# Meteo_shema_32F407.net
KiCad netlist of a schematic drawn in Altium Designer
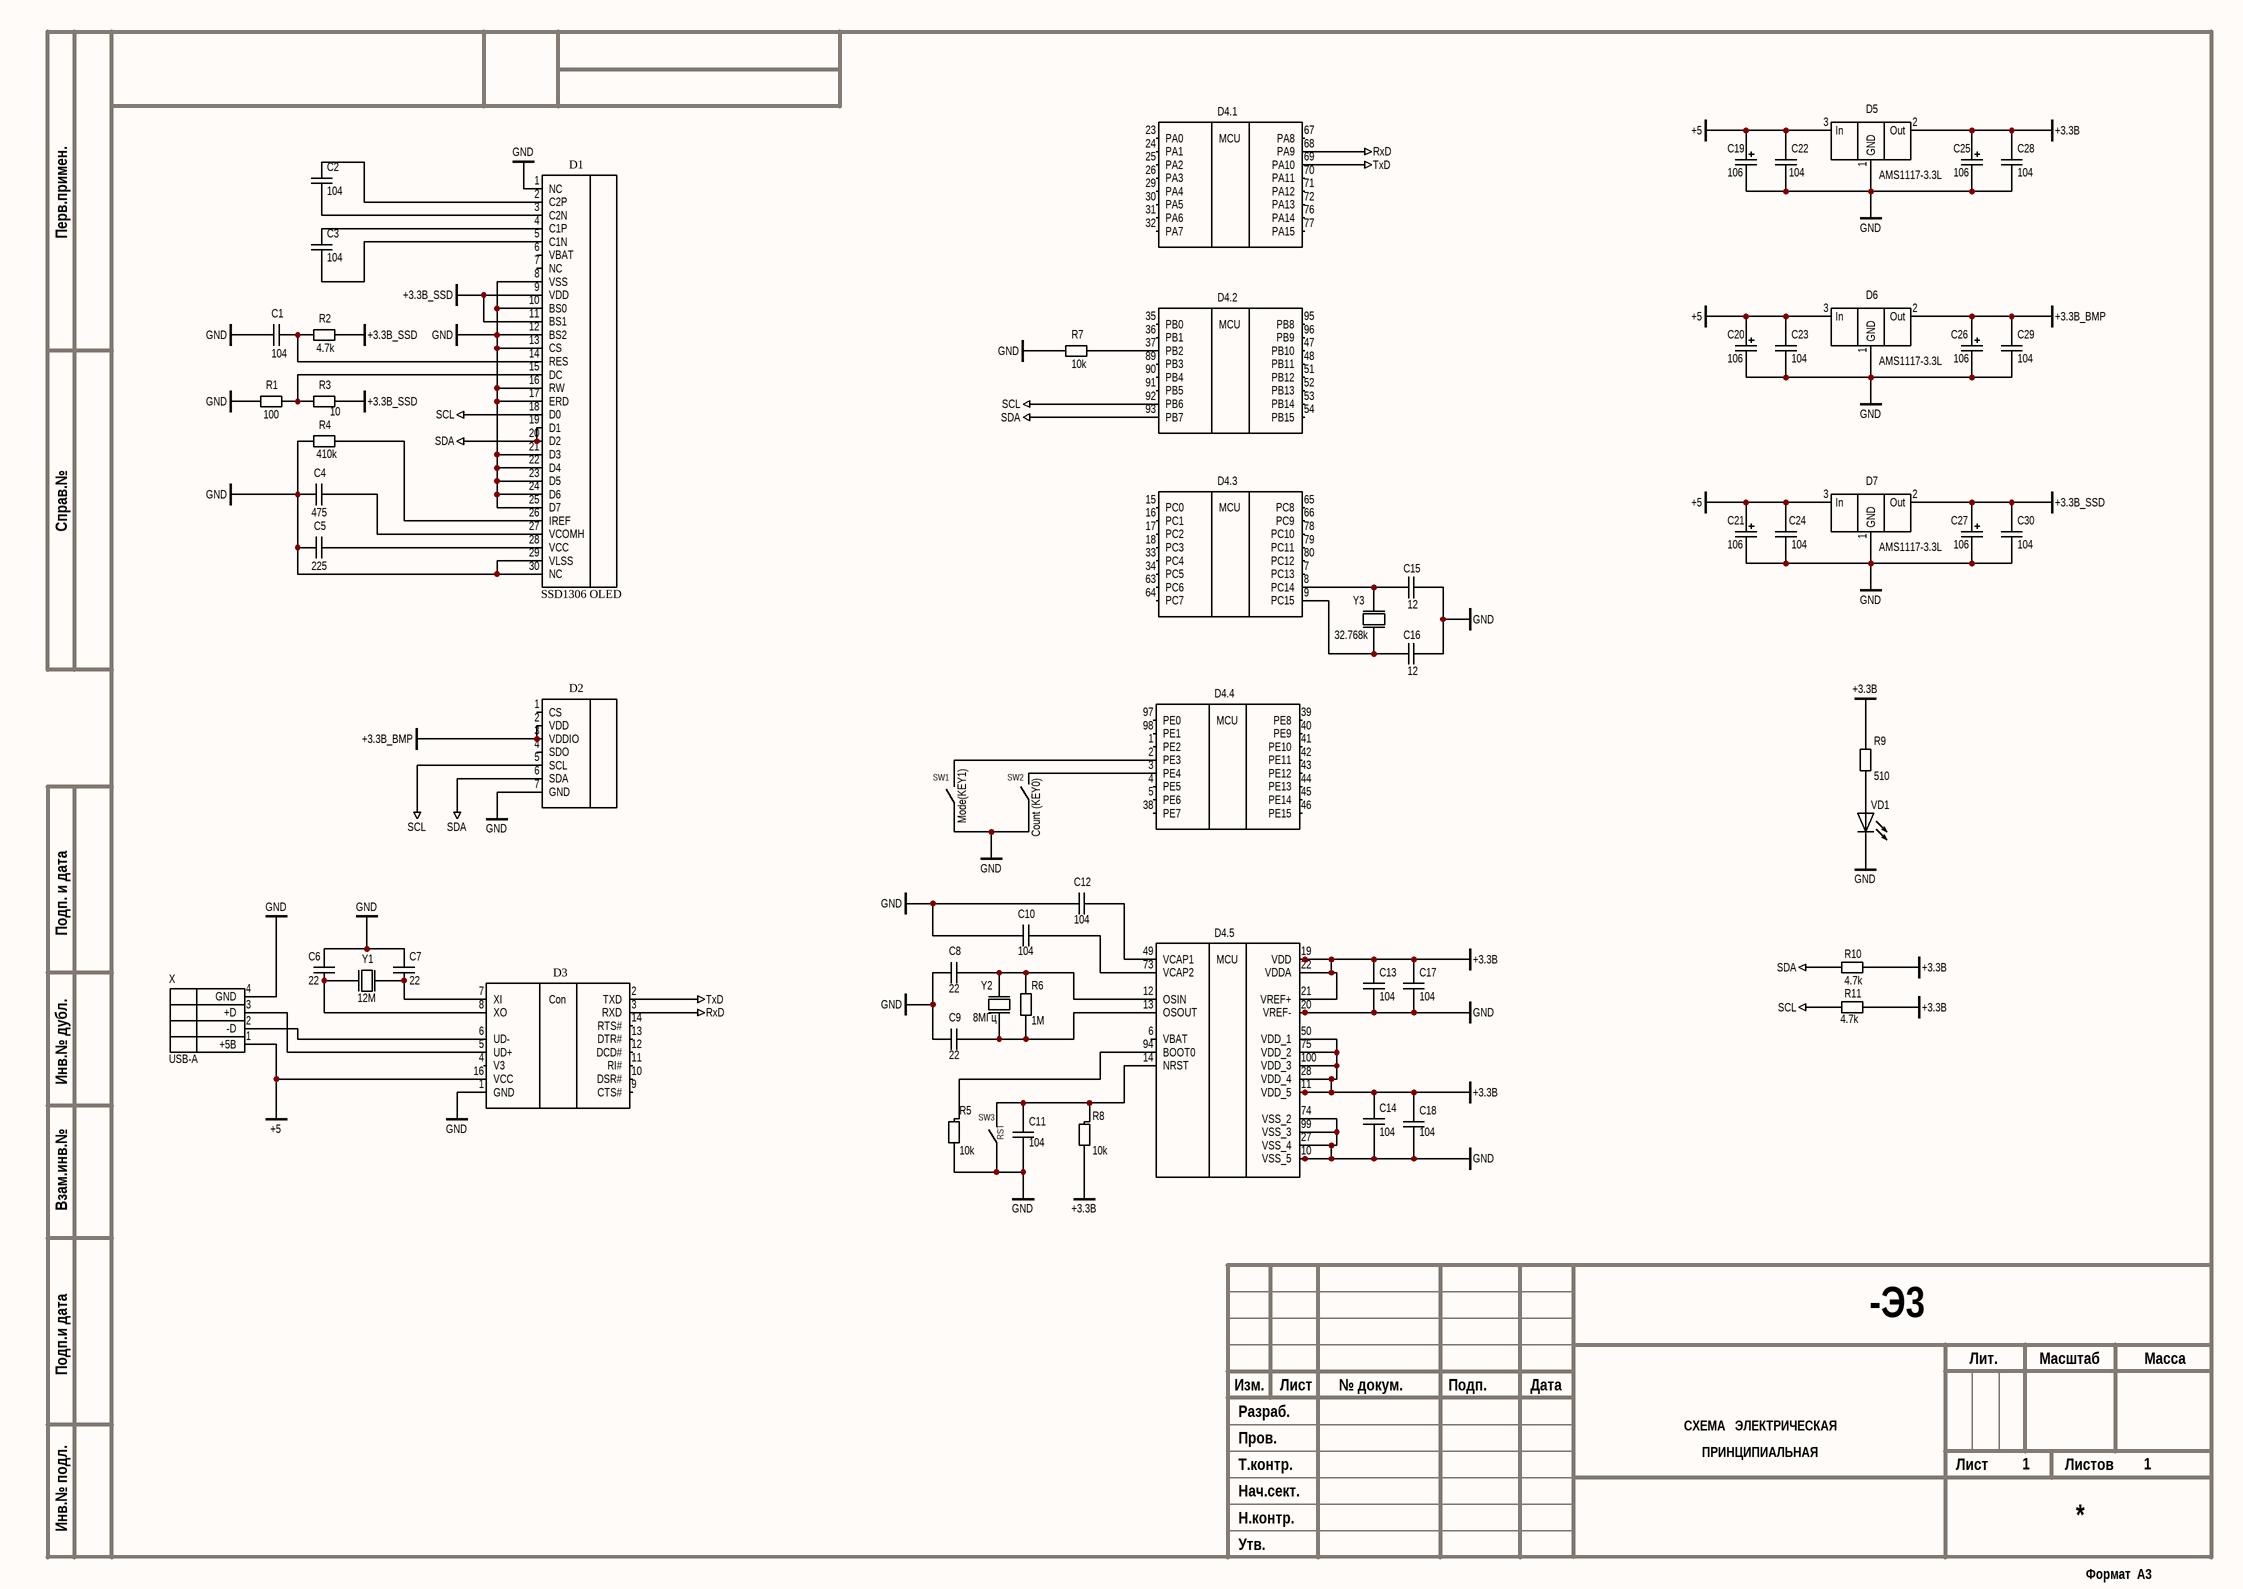
[diagram p0: Meteo_shema_32F407.SchDoc]

(export (version "E")
  (design (tool "Eeschema 10.0.6"))
  (components
    (comp (ref "C1") (value "104") (footprint "0603") (libsource (lib "MainLib") (part "C")))
    (comp (ref "C2") (value "104") (footprint "0603") (libsource (lib "MainLib") (part "C")))
    (comp (ref "C3") (value "104") (footprint "0603") (libsource (lib "MainLib") (part "C")))
    (comp (ref "C4") (value "475") (footprint "0603") (libsource (lib "MainLib") (part "C")))
    (comp (ref "C5") (value "225") (footprint "0603") (libsource (lib "MainLib") (part "C")))
    (comp (ref "C6") (value "22") (footprint "0603") (libsource (lib "MainLib") (part "C")))
    (comp (ref "C7") (value "22") (footprint "0603") (libsource (lib "MainLib") (part "C")))
    (comp (ref "C8") (value "22") (footprint "0603") (libsource (lib "MainLib") (part "C")))
    (comp (ref "C9") (value "22") (footprint "0603") (libsource (lib "MainLib") (part "C")))
    (comp (ref "C11") (value "104") (footprint "0603") (libsource (lib "MainLib") (part "C")))
    (comp (ref "C12") (value "104") (footprint "0603") (libsource (lib "MainLib") (part "C")))
    (comp (ref "C13") (value "104") (footprint "0603") (libsource (lib "MainLib") (part "C")))
    (comp (ref "C14") (value "104") (footprint "0603") (libsource (lib "MainLib") (part "C")))
    (comp (ref "C15") (value "12") (footprint "0603") (libsource (lib "MainLib") (part "C")))
    (comp (ref "C16") (value "12") (footprint "0603") (libsource (lib "MainLib") (part "C")))
    (comp (ref "C17") (value "104") (footprint "0603") (libsource (lib "MainLib") (part "C")))
    (comp (ref "C18") (value "104") (footprint "0603") (libsource (lib "MainLib") (part "C")))
    (comp (ref "C19")
      (value "106")
      (footprint "EIA_6032–28")
      (description "TECAP EIA 6032–28")
      (libsource (lib "MainLib") (part "C+ TECAP"))
    )
    (comp (ref "C20")
      (value "106")
      (footprint "EIA_6032–28")
      (description "TECAP EIA 6032–28")
      (libsource (lib "MainLib") (part "C+ TECAP"))
    )
    (comp (ref "C21")
      (value "106")
      (footprint "EIA_6032–28")
      (description "TECAP EIA 6032–28")
      (libsource (lib "MainLib") (part "C+ TECAP"))
    )
    (comp (ref "C22") (value "104") (footprint "0603") (libsource (lib "MainLib") (part "C")))
    (comp (ref "C23") (value "104") (footprint "0603") (libsource (lib "MainLib") (part "C")))
    (comp (ref "C24") (value "104") (footprint "0603") (libsource (lib "MainLib") (part "C")))
    (comp (ref "C25")
      (value "106")
      (footprint "EIA_6032–28")
      (description "TECAP EIA 6032–28")
      (libsource (lib "MainLib") (part "C+ TECAP"))
    )
    (comp (ref "C26")
      (value "106")
      (footprint "EIA_6032–28")
      (description "TECAP EIA 6032–28")
      (libsource (lib "MainLib") (part "C+ TECAP"))
    )
    (comp (ref "C27")
      (value "106")
      (footprint "EIA_6032–28")
      (description "TECAP EIA 6032–28")
      (libsource (lib "MainLib") (part "C+ TECAP"))
    )
    (comp (ref "C28") (value "104") (footprint "0603") (libsource (lib "MainLib") (part "C")))
    (comp (ref "C29") (value "104") (footprint "0603") (libsource (lib "MainLib") (part "C")))
    (comp (ref "C30") (value "104") (footprint "0603") (libsource (lib "MainLib") (part "C")))
    (comp (ref "D1")
      (value "SSD1306 OLED")
      (footprint "SSD1306")
      (libsource (lib "MainLib") (part "SSD1306 OLED"))
    )
    (comp (ref "D2") (value "BMP180") (footprint "BMP180") (libsource (lib "MainLib") (part "BMP180")))
    (comp (ref "D3") (value "CH340G") (libsource (lib "MainLib") (part "CH340G")))
    (comp (ref "D4")
      (value "STM32F407VE")
      (footprint "LQFP100")
      (description "ARM3")
      (libsource (lib "MainLib") (part "STM32F407VE"))
    )
    (comp (ref "D5")
      (value "AMS1117-3.3L")
      (footprint "SOT223-4N")
      (libsource (lib "MainLib") (part "AMS1117-3.3L"))
    )
    (comp (ref "D6")
      (value "AMS1117-3.3L")
      (footprint "SOT223-4N")
      (libsource (lib "MainLib") (part "AMS1117-3.3L"))
    )
    (comp (ref "D7")
      (value "AMS1117-3.3L")
      (footprint "SOT223-4N")
      (libsource (lib "MainLib") (part "AMS1117-3.3L"))
    )
    (comp (ref "R1") (value "100") (footprint "0603") (libsource (lib "MainLib") (part "R")))
    (comp (ref "R2") (value "4.7k") (footprint "0603") (libsource (lib "MainLib") (part "R")))
    (comp (ref "R3") (value "10") (footprint "0603") (libsource (lib "MainLib") (part "R")))
    (comp (ref "R4") (value "410k") (footprint "0603") (libsource (lib "MainLib") (part "R")))
    (comp (ref "R5") (value "10k") (footprint "0603") (libsource (lib "MainLib") (part "R")))
    (comp (ref "R6") (value "1M") (footprint "0603") (libsource (lib "MainLib") (part "R")))
    (comp (ref "R7") (value "10k") (footprint "0603") (libsource (lib "MainLib") (part "R")))
    (comp (ref "R8") (value "10k") (footprint "0603") (libsource (lib "MainLib") (part "R")))
    (comp (ref "R9") (value "510") (footprint "0603") (libsource (lib "MainLib") (part "R")))
    (comp (ref "R10") (value "4.7k") (footprint "0603") (libsource (lib "MainLib") (part "R")))
    (comp (ref "R11") (value "4.7k") (footprint "0603") (libsource (lib "MainLib") (part "R")))
    (comp (ref "SW1") (value "Mode(KEY1)") (footprint "0603") (libsource (lib "MainLib") (part "Button")))
    (comp (ref "SW2") (value "Count (KEY0)") (footprint "0603") (libsource (lib "MainLib") (part "Button")))
    (comp (ref "SW3") (value "RST") (footprint "0603") (libsource (lib "MainLib") (part "Button")))
    (comp (ref "VD1")
      (value "LED SMD 0805")
      (footprint "Led Diode 0805")
      (libsource (lib "MainLib") (part "LED SMD 0805"))
    )
    (comp (ref "X")
      (value "USB-A")
      (footprint "USB-ASM (DS1098-B)")
      (libsource (lib "MainLib") (part "USB-A"))
    )
    (comp (ref "Y1") (value "12M") (footprint "HC-49SM") (libsource (lib "MainLib") (part "BQ")))
    (comp (ref "Y2") (value "8МГц") (footprint "HC-49SM") (libsource (lib "MainLib") (part "BQ")))
    (comp (ref "Y3") (value "32.768k") (footprint "HC-49SM") (libsource (lib "MainLib") (part "BQ")))
    (comp (ref "С10") (value "104") (footprint "0603") (libsource (lib "MainLib") (part "C")))
  )
  (nets
    (net (code "1") (name "+3.3В") (class "Default")
      (node (ref "C13") (pin "1") (pinfunction "1_1") (pintype "passive"))
      (node (ref "C14") (pin "1") (pinfunction "1_1") (pintype "passive"))
      (node (ref "C17") (pin "1") (pinfunction "1_1") (pintype "passive"))
      (node (ref "C18") (pin "1") (pinfunction "1_1") (pintype "passive"))
      (node (ref "C25") (pin "1") (pinfunction "1_1") (pintype "passive"))
      (node (ref "C28") (pin "2") (pinfunction "2_2") (pintype "passive"))
      (node (ref "D4") (pin "100") (pinfunction "VDD_3_100") (pintype "passive"))
      (node (ref "D4") (pin "11") (pinfunction "VDD_5_11") (pintype "passive"))
      (node (ref "D4") (pin "19") (pinfunction "VDD_19") (pintype "passive"))
      (node (ref "D4") (pin "21") (pinfunction "VREF+_21") (pintype "passive"))
      (node (ref "D4") (pin "22") (pinfunction "VDDA_22") (pintype "passive"))
      (node (ref "D4") (pin "28") (pinfunction "VDD_4_28") (pintype "passive"))
      (node (ref "D4") (pin "50") (pinfunction "VDD_1_50") (pintype "passive"))
      (node (ref "D4") (pin "75") (pinfunction "VDD_2_75") (pintype "passive"))
      (node (ref "D5") (pin "2") (pinfunction "Out_2") (pintype "passive"))
      (node (ref "R10") (pin "2") (pinfunction "2_2") (pintype "passive"))
      (node (ref "R11") (pin "2") (pinfunction "2_2") (pintype "passive"))
      (node (ref "R8") (pin "2") (pinfunction "2_2") (pintype "passive"))
      (node (ref "R9") (pin "1") (pinfunction "1_1") (pintype "passive"))
    )
    (net (code "2") (name "+3.3В_BMP") (class "Default")
      (node (ref "C26") (pin "1") (pinfunction "1_1") (pintype "passive"))
      (node (ref "C29") (pin "2") (pinfunction "2_2") (pintype "passive"))
      (node (ref "D2") (pin "2") (pinfunction "VDD_2") (pintype "passive"))
      (node (ref "D2") (pin "3") (pinfunction "VDDIO_3") (pintype "passive"))
      (node (ref "D6") (pin "2") (pinfunction "Out_2") (pintype "passive"))
    )
    (net (code "3") (name "+3.3В_SSD") (class "Default")
      (node (ref "C27") (pin "1") (pinfunction "1_1") (pintype "passive"))
      (node (ref "C30") (pin "2") (pinfunction "2_2") (pintype "passive"))
      (node (ref "D1") (pin "11") (pinfunction "BS1_11") (pintype "passive"))
      (node (ref "D1") (pin "9") (pinfunction "VDD_9") (pintype "passive"))
      (node (ref "D7") (pin "2") (pinfunction "Out_2") (pintype "passive"))
      (node (ref "R2") (pin "1") (pinfunction "1_1") (pintype "passive"))
      (node (ref "R3") (pin "1") (pinfunction "1_1") (pintype "passive"))
    )
    (net (code "4") (name "+5") (class "Default")
      (node (ref "C19") (pin "1") (pinfunction "1_1") (pintype "passive"))
      (node (ref "C20") (pin "1") (pinfunction "1_1") (pintype "passive"))
      (node (ref "C21") (pin "1") (pinfunction "1_1") (pintype "passive"))
      (node (ref "C22") (pin "2") (pinfunction "2_2") (pintype "passive"))
      (node (ref "C23") (pin "2") (pinfunction "2_2") (pintype "passive"))
      (node (ref "C24") (pin "2") (pinfunction "2_2") (pintype "passive"))
      (node (ref "D3") (pin "16") (pinfunction "VCC_16") (pintype "passive"))
      (node (ref "D5") (pin "3") (pinfunction "In_3") (pintype "passive"))
      (node (ref "D6") (pin "3") (pinfunction "In_3") (pintype "passive"))
      (node (ref "D7") (pin "3") (pinfunction "In_3") (pintype "passive"))
      (node (ref "X") (pin "1") (pinfunction "+5В_1") (pintype "passive"))
    )
    (net (code "5") (name "GND") (class "Default")
      (node (ref "C1") (pin "1") (pinfunction "1_1") (pintype "passive"))
      (node (ref "C11") (pin "1") (pinfunction "1_1") (pintype "passive"))
      (node (ref "C12") (pin "2") (pinfunction "2_2") (pintype "passive"))
      (node (ref "C13") (pin "2") (pinfunction "2_2") (pintype "passive"))
      (node (ref "C14") (pin "2") (pinfunction "2_2") (pintype "passive"))
      (node (ref "C15") (pin "1") (pinfunction "1_1") (pintype "passive"))
      (node (ref "C16") (pin "1") (pinfunction "1_1") (pintype "passive"))
      (node (ref "C17") (pin "2") (pinfunction "2_2") (pintype "passive"))
      (node (ref "C18") (pin "2") (pinfunction "2_2") (pintype "passive"))
      (node (ref "C19") (pin "2") (pinfunction "2_2") (pintype "passive"))
      (node (ref "C20") (pin "2") (pinfunction "2_2") (pintype "passive"))
      (node (ref "C21") (pin "2") (pinfunction "2_2") (pintype "passive"))
      (node (ref "C22") (pin "1") (pinfunction "1_1") (pintype "passive"))
      (node (ref "C23") (pin "1") (pinfunction "1_1") (pintype "passive"))
      (node (ref "C24") (pin "1") (pinfunction "1_1") (pintype "passive"))
      (node (ref "C25") (pin "2") (pinfunction "2_2") (pintype "passive"))
      (node (ref "C26") (pin "2") (pinfunction "2_2") (pintype "passive"))
      (node (ref "C27") (pin "2") (pinfunction "2_2") (pintype "passive"))
      (node (ref "C28") (pin "1") (pinfunction "1_1") (pintype "passive"))
      (node (ref "C29") (pin "1") (pinfunction "1_1") (pintype "passive"))
      (node (ref "C30") (pin "1") (pinfunction "1_1") (pintype "passive"))
      (node (ref "C4") (pin "1") (pinfunction "1_1") (pintype "passive"))
      (node (ref "C5") (pin "1") (pinfunction "1_1") (pintype "passive"))
      (node (ref "C6") (pin "2") (pinfunction "2_2") (pintype "passive"))
      (node (ref "C7") (pin "2") (pinfunction "2_2") (pintype "passive"))
      (node (ref "C8") (pin "2") (pinfunction "2_2") (pintype "passive"))
      (node (ref "C9") (pin "2") (pinfunction "2_2") (pintype "passive"))
      (node (ref "D1") (pin "1") (pinfunction "NC_1") (pintype "passive"))
      (node (ref "D1") (pin "10") (pinfunction "BS0_10") (pintype "passive"))
      (node (ref "D1") (pin "12") (pinfunction "BS2_12") (pintype "passive"))
      (node (ref "D1") (pin "13") (pinfunction "CS_13") (pintype "passive"))
      (node (ref "D1") (pin "16") (pinfunction "RW_16") (pintype "passive"))
      (node (ref "D1") (pin "17") (pinfunction "ERD_17") (pintype "passive"))
      (node (ref "D1") (pin "21") (pinfunction "D3_21") (pintype "passive"))
      (node (ref "D1") (pin "22") (pinfunction "D4_22") (pintype "passive"))
      (node (ref "D1") (pin "23") (pinfunction "D5_23") (pintype "passive"))
      (node (ref "D1") (pin "24") (pinfunction "D6_24") (pintype "passive"))
      (node (ref "D1") (pin "25") (pinfunction "D7_25") (pintype "passive"))
      (node (ref "D1") (pin "29") (pinfunction "VLSS_29") (pintype "passive"))
      (node (ref "D1") (pin "30") (pinfunction "NC_30") (pintype "passive"))
      (node (ref "D1") (pin "8") (pinfunction "VSS_8") (pintype "passive"))
      (node (ref "D2") (pin "7") (pinfunction "GND_7") (pintype "passive"))
      (node (ref "D3") (pin "1") (pinfunction "GND_1") (pintype "passive"))
      (node (ref "D4") (pin "10") (pinfunction "VSS_5_10") (pintype "passive"))
      (node (ref "D4") (pin "20") (pinfunction "VREF-_20") (pintype "passive"))
      (node (ref "D4") (pin "27") (pinfunction "VSS_4_27") (pintype "passive"))
      (node (ref "D4") (pin "74") (pinfunction "VSS_2_74") (pintype "passive"))
      (node (ref "D4") (pin "99") (pinfunction "VSS_3_99") (pintype "passive"))
      (node (ref "D5") (pin "1") (pinfunction "GND_1") (pintype "passive"))
      (node (ref "D6") (pin "1") (pinfunction "GND_1") (pintype "passive"))
      (node (ref "D7") (pin "1") (pinfunction "GND_1") (pintype "passive"))
      (node (ref "R1") (pin "2") (pinfunction "2_2") (pintype "passive"))
      (node (ref "R4") (pin "2") (pinfunction "2_2") (pintype "passive"))
      (node (ref "R5") (pin "2") (pinfunction "2_2") (pintype "passive"))
      (node (ref "R7") (pin "1") (pinfunction "1_1") (pintype "passive"))
      (node (ref "SW1") (pin "1") (pinfunction "1_1") (pintype "passive"))
      (node (ref "SW2") (pin "1") (pinfunction "1_1") (pintype "passive"))
      (node (ref "SW3") (pin "1") (pinfunction "1_1") (pintype "passive"))
      (node (ref "VD1") (pin "K") (pinfunction "K_K") (pintype "passive"))
      (node (ref "X") (pin "4") (pinfunction "GND_4") (pintype "passive"))
      (node (ref "С10") (pin "2") (pinfunction "2_2") (pintype "passive"))
    )
    (net (code "6") (name "Net-(D1-C1N)") (class "Default")
      (node (ref "C3") (pin "2") (pinfunction "2_2") (pintype "passive"))
      (node (ref "D1") (pin "5") (pinfunction "C1N_5") (pintype "passive"))
    )
    (net (code "7") (name "Net-(D1-C1P)") (class "Default")
      (node (ref "C3") (pin "1") (pinfunction "1_1") (pintype "passive"))
      (node (ref "D1") (pin "4") (pinfunction "C1P_4") (pintype "passive"))
    )
    (net (code "8") (name "Net-(D1-C2N)") (class "Default")
      (node (ref "C2") (pin "2") (pinfunction "2_2") (pintype "passive"))
      (node (ref "D1") (pin "3") (pinfunction "C2N_3") (pintype "passive"))
    )
    (net (code "9") (name "Net-(D1-C2P)") (class "Default")
      (node (ref "C2") (pin "1") (pinfunction "1_1") (pintype "passive"))
      (node (ref "D1") (pin "2") (pinfunction "C2P_2") (pintype "passive"))
    )
    (net (code "10") (name "Net-(D1-DC)") (class "Default")
      (node (ref "D1") (pin "15") (pinfunction "DC_15") (pintype "passive"))
      (node (ref "R1") (pin "1") (pinfunction "1_1") (pintype "passive"))
      (node (ref "R3") (pin "2") (pinfunction "2_2") (pintype "passive"))
    )
    (net (code "11") (name "Net-(D1-IREF)") (class "Default")
      (node (ref "D1") (pin "26") (pinfunction "IREF_26") (pintype "passive"))
      (node (ref "R4") (pin "1") (pinfunction "1_1") (pintype "passive"))
    )
    (net (code "12") (name "Net-(D1-RES)") (class "Default")
      (node (ref "C1") (pin "2") (pinfunction "2_2") (pintype "passive"))
      (node (ref "D1") (pin "14") (pinfunction "RES_14") (pintype "passive"))
      (node (ref "R2") (pin "2") (pinfunction "2_2") (pintype "passive"))
    )
    (net (code "13") (name "Net-(D1-VCC)") (class "Default")
      (node (ref "C5") (pin "2") (pinfunction "2_2") (pintype "passive"))
      (node (ref "D1") (pin "28") (pinfunction "VCC_28") (pintype "passive"))
    )
    (net (code "14") (name "Net-(D1-VCOMH)") (class "Default")
      (node (ref "C4") (pin "2") (pinfunction "2_2") (pintype "passive"))
      (node (ref "D1") (pin "27") (pinfunction "VCOMH_27") (pintype "passive"))
    )
    (net (code "15") (name "Net-(D3-UD+)") (class "Default")
      (node (ref "D3") (pin "5") (pinfunction "UD+_5") (pintype "passive"))
      (node (ref "X") (pin "3") (pinfunction "+D_3") (pintype "passive"))
    )
    (net (code "16") (name "Net-(D3-UD-)") (class "Default")
      (node (ref "D3") (pin "6") (pinfunction "UD-_6") (pintype "passive"))
      (node (ref "X") (pin "2") (pinfunction "-D_2") (pintype "passive"))
    )
    (net (code "17") (name "Net-(D3-XI)") (class "Default")
      (node (ref "C7") (pin "1") (pinfunction "1_1") (pintype "passive"))
      (node (ref "D3") (pin "7") (pinfunction "XI_7") (pintype "passive"))
      (node (ref "Y1") (pin "1") (pinfunction "1_1") (pintype "passive"))
    )
    (net (code "18") (name "Net-(D3-XO)") (class "Default")
      (node (ref "C6") (pin "1") (pinfunction "1_1") (pintype "passive"))
      (node (ref "D3") (pin "8") (pinfunction "XO_8") (pintype "passive"))
      (node (ref "Y1") (pin "2") (pinfunction "2_2") (pintype "passive"))
    )
    (net (code "19") (name "Net-(D4B-PB2)") (class "Default")
      (node (ref "D4") (pin "37") (pinfunction "PB2_37") (pintype "passive"))
      (node (ref "R7") (pin "2") (pinfunction "2_2") (pintype "passive"))
    )
    (net (code "20") (name "Net-(D4C-PC14)") (class "Default")
      (node (ref "C15") (pin "2") (pinfunction "2_2") (pintype "passive"))
      (node (ref "D4") (pin "8") (pinfunction "PC14_8") (pintype "passive"))
      (node (ref "Y3") (pin "2") (pinfunction "2_2") (pintype "passive"))
    )
    (net (code "21") (name "Net-(D4C-PC15)") (class "Default")
      (node (ref "C16") (pin "2") (pinfunction "2_2") (pintype "passive"))
      (node (ref "D4") (pin "9") (pinfunction "PC15_9") (pintype "passive"))
      (node (ref "Y3") (pin "1") (pinfunction "1_1") (pintype "passive"))
    )
    (net (code "22") (name "Net-(D4E-PE3)") (class "Default")
      (node (ref "D4") (pin "2") (pinfunction "PE3_2") (pintype "passive"))
      (node (ref "SW1") (pin "2") (pinfunction "2_2") (pintype "passive"))
    )
    (net (code "23") (name "Net-(D4E-PE4)") (class "Default")
      (node (ref "D4") (pin "3") (pinfunction "PE4_3") (pintype "passive"))
      (node (ref "SW2") (pin "2") (pinfunction "2_2") (pintype "passive"))
    )
    (net (code "24") (name "Net-(D4F-BOOT0)") (class "Default")
      (node (ref "D4") (pin "94") (pinfunction "BOOT0_94") (pintype "passive"))
      (node (ref "R5") (pin "1") (pinfunction "1_1") (pintype "passive"))
    )
    (net (code "25") (name "Net-(D4F-NRST)") (class "Default")
      (node (ref "C11") (pin "2") (pinfunction "2_2") (pintype "passive"))
      (node (ref "D4") (pin "14") (pinfunction "NRST_14") (pintype "passive"))
      (node (ref "R8") (pin "1") (pinfunction "1_1") (pintype "passive"))
      (node (ref "SW3") (pin "2") (pinfunction "2_2") (pintype "passive"))
    )
    (net (code "26") (name "Net-(D4F-OSIN)") (class "Default")
      (node (ref "C8") (pin "1") (pinfunction "1_1") (pintype "passive"))
      (node (ref "D4") (pin "12") (pinfunction "OSIN_12") (pintype "passive"))
      (node (ref "R6") (pin "2") (pinfunction "2_2") (pintype "passive"))
      (node (ref "Y2") (pin "2") (pinfunction "2_2") (pintype "passive"))
    )
    (net (code "27") (name "Net-(D4F-OSOUT)") (class "Default")
      (node (ref "C9") (pin "1") (pinfunction "1_1") (pintype "passive"))
      (node (ref "D4") (pin "13") (pinfunction "OSOUT_13") (pintype "passive"))
      (node (ref "R6") (pin "1") (pinfunction "1_1") (pintype "passive"))
      (node (ref "Y2") (pin "1") (pinfunction "1_1") (pintype "passive"))
    )
    (net (code "28") (name "Net-(D4F-VCAP1)") (class "Default")
      (node (ref "C12") (pin "1") (pinfunction "1_1") (pintype "passive"))
      (node (ref "D4") (pin "49") (pinfunction "VCAP1_49") (pintype "passive"))
    )
    (net (code "29") (name "Net-(D4F-VCAP2)") (class "Default")
      (node (ref "D4") (pin "73") (pinfunction "VCAP2_73") (pintype "passive"))
      (node (ref "С10") (pin "1") (pinfunction "1_1") (pintype "passive"))
    )
    (net (code "30") (name "Net-(R9-Pad2)") (class "Default")
      (node (ref "R9") (pin "2") (pinfunction "2_2") (pintype "passive"))
      (node (ref "VD1") (pin "A") (pinfunction "A_A") (pintype "passive"))
    )
    (net (code "31") (name "RxD") (class "Default")
      (node (ref "D3") (pin "3") (pinfunction "RXD_3") (pintype "passive"))
      (node (ref "D4") (pin "68") (pinfunction "PA9_68") (pintype "passive"))
    )
    (net (code "32") (name "SCL") (class "Default")
      (node (ref "D1") (pin "18") (pinfunction "D0_18") (pintype "passive"))
      (node (ref "D2") (pin "5") (pinfunction "SCL_5") (pintype "passive"))
      (node (ref "D4") (pin "92") (pinfunction "PB6_92") (pintype "passive"))
      (node (ref "R11") (pin "1") (pinfunction "1_1") (pintype "passive"))
    )
    (net (code "33") (name "SDA") (class "Default")
      (node (ref "D1") (pin "19") (pinfunction "D1_19") (pintype "passive"))
      (node (ref "D1") (pin "20") (pinfunction "D2_20") (pintype "passive"))
      (node (ref "D2") (pin "6") (pinfunction "SDA_6") (pintype "passive"))
      (node (ref "D4") (pin "93") (pinfunction "PB7_93") (pintype "passive"))
      (node (ref "R10") (pin "1") (pinfunction "1_1") (pintype "passive"))
    )
    (net (code "34") (name "TxD") (class "Default")
      (node (ref "D3") (pin "2") (pinfunction "TXD_2") (pintype "passive"))
      (node (ref "D4") (pin "69") (pinfunction "PA10_69") (pintype "passive"))
    )
    (net (code "35") (name "unconnected-(D1-NC-Pad7)") (class "Default")
      (node (ref "D1") (pin "7") (pinfunction "NC_7") (pintype "passive"))
    )
    (net (code "36") (name "unconnected-(D1-VBAT-Pad6)") (class "Default")
      (node (ref "D1") (pin "6") (pinfunction "VBAT_6") (pintype "passive"))
    )
    (net (code "37") (name "unconnected-(D2-CS-Pad1)") (class "Default")
      (node (ref "D2") (pin "1") (pinfunction "CS_1") (pintype "passive"))
    )
    (net (code "38") (name "unconnected-(D2-SDO-Pad4)") (class "Default")
      (node (ref "D2") (pin "4") (pinfunction "SDO_4") (pintype "passive"))
    )
    (net (code "39") (name "unconnected-(D3-CTS#-Pad9)") (class "Default")
      (node (ref "D3") (pin "9") (pinfunction "CTS#_9") (pintype "passive"))
    )
    (net (code "40") (name "unconnected-(D3-DCD#-Pad12)") (class "Default")
      (node (ref "D3") (pin "12") (pinfunction "DCD#_12") (pintype "passive"))
    )
    (net (code "41") (name "unconnected-(D3-DSR#-Pad10)") (class "Default")
      (node (ref "D3") (pin "10") (pinfunction "DSR#_10") (pintype "passive"))
    )
    (net (code "42") (name "unconnected-(D3-DTR#-Pad13)") (class "Default")
      (node (ref "D3") (pin "13") (pinfunction "DTR#_13") (pintype "passive"))
    )
    (net (code "43") (name "unconnected-(D3-RI#-Pad11)") (class "Default")
      (node (ref "D3") (pin "11") (pinfunction "RI#_11") (pintype "passive"))
    )
    (net (code "44") (name "unconnected-(D3-RTS#-Pad14)") (class "Default")
      (node (ref "D3") (pin "14") (pinfunction "RTS#_14") (pintype "passive"))
    )
    (net (code "45") (name "unconnected-(D3-V3-Pad4)") (class "Default")
      (node (ref "D3") (pin "4") (pinfunction "V3_4") (pintype "passive"))
    )
    (net (code "46") (name "unconnected-(D4A-PA0-Pad23)") (class "Default")
      (node (ref "D4") (pin "23") (pinfunction "PA0_23") (pintype "passive"))
    )
    (net (code "47") (name "unconnected-(D4A-PA1-Pad24)") (class "Default")
      (node (ref "D4") (pin "24") (pinfunction "PA1_24") (pintype "passive"))
    )
    (net (code "48") (name "unconnected-(D4A-PA2-Pad25)") (class "Default")
      (node (ref "D4") (pin "25") (pinfunction "PA2_25") (pintype "passive"))
    )
    (net (code "49") (name "unconnected-(D4A-PA3-Pad26)") (class "Default")
      (node (ref "D4") (pin "26") (pinfunction "PA3_26") (pintype "passive"))
    )
    (net (code "50") (name "unconnected-(D4A-PA4-Pad29)") (class "Default")
      (node (ref "D4") (pin "29") (pinfunction "PA4_29") (pintype "passive"))
    )
    (net (code "51") (name "unconnected-(D4A-PA5-Pad30)") (class "Default")
      (node (ref "D4") (pin "30") (pinfunction "PA5_30") (pintype "passive"))
    )
    (net (code "52") (name "unconnected-(D4A-PA6-Pad31)") (class "Default")
      (node (ref "D4") (pin "31") (pinfunction "PA6_31") (pintype "passive"))
    )
    (net (code "53") (name "unconnected-(D4A-PA7-Pad32)") (class "Default")
      (node (ref "D4") (pin "32") (pinfunction "PA7_32") (pintype "passive"))
    )
    (net (code "54") (name "unconnected-(D4A-PA8-Pad67)") (class "Default")
      (node (ref "D4") (pin "67") (pinfunction "PA8_67") (pintype "passive"))
    )
    (net (code "55") (name "unconnected-(D4A-PA11-Pad70)") (class "Default")
      (node (ref "D4") (pin "70") (pinfunction "PA11_70") (pintype "passive"))
    )
    (net (code "56") (name "unconnected-(D4A-PA12-Pad71)") (class "Default")
      (node (ref "D4") (pin "71") (pinfunction "PA12_71") (pintype "passive"))
    )
    (net (code "57") (name "unconnected-(D4A-PA13-Pad72)") (class "Default")
      (node (ref "D4") (pin "72") (pinfunction "PA13_72") (pintype "passive"))
    )
    (net (code "58") (name "unconnected-(D4A-PA14-Pad76)") (class "Default")
      (node (ref "D4") (pin "76") (pinfunction "PA14_76") (pintype "passive"))
    )
    (net (code "59") (name "unconnected-(D4A-PA15-Pad77)") (class "Default")
      (node (ref "D4") (pin "77") (pinfunction "PA15_77") (pintype "passive"))
    )
    (net (code "60") (name "unconnected-(D4B-PB0-Pad35)") (class "Default")
      (node (ref "D4") (pin "35") (pinfunction "PB0_35") (pintype "passive"))
    )
    (net (code "61") (name "unconnected-(D4B-PB1-Pad36)") (class "Default")
      (node (ref "D4") (pin "36") (pinfunction "PB1_36") (pintype "passive"))
    )
    (net (code "62") (name "unconnected-(D4B-PB3-Pad89)") (class "Default")
      (node (ref "D4") (pin "89") (pinfunction "PB3_89") (pintype "passive"))
    )
    (net (code "63") (name "unconnected-(D4B-PB4-Pad90)") (class "Default")
      (node (ref "D4") (pin "90") (pinfunction "PB4_90") (pintype "passive"))
    )
    (net (code "64") (name "unconnected-(D4B-PB5-Pad91)") (class "Default")
      (node (ref "D4") (pin "91") (pinfunction "PB5_91") (pintype "passive"))
    )
    (net (code "65") (name "unconnected-(D4B-PB8-Pad95)") (class "Default")
      (node (ref "D4") (pin "95") (pinfunction "PB8_95") (pintype "passive"))
    )
    (net (code "66") (name "unconnected-(D4B-PB9-Pad96)") (class "Default")
      (node (ref "D4") (pin "96") (pinfunction "PB9_96") (pintype "passive"))
    )
    (net (code "67") (name "unconnected-(D4B-PB10-Pad47)") (class "Default")
      (node (ref "D4") (pin "47") (pinfunction "PB10_47") (pintype "passive"))
    )
    (net (code "68") (name "unconnected-(D4B-PB11-Pad48)") (class "Default")
      (node (ref "D4") (pin "48") (pinfunction "PB11_48") (pintype "passive"))
    )
    (net (code "69") (name "unconnected-(D4B-PB12-Pad51)") (class "Default")
      (node (ref "D4") (pin "51") (pinfunction "PB12_51") (pintype "passive"))
    )
    (net (code "70") (name "unconnected-(D4B-PB13-Pad52)") (class "Default")
      (node (ref "D4") (pin "52") (pinfunction "PB13_52") (pintype "passive"))
    )
    (net (code "71") (name "unconnected-(D4B-PB14-Pad53)") (class "Default")
      (node (ref "D4") (pin "53") (pinfunction "PB14_53") (pintype "passive"))
    )
    (net (code "72") (name "unconnected-(D4B-PB15-Pad54)") (class "Default")
      (node (ref "D4") (pin "54") (pinfunction "PB15_54") (pintype "passive"))
    )
    (net (code "73") (name "unconnected-(D4C-PC0-Pad15)") (class "Default")
      (node (ref "D4") (pin "15") (pinfunction "PC0_15") (pintype "passive"))
    )
    (net (code "74") (name "unconnected-(D4C-PC1-Pad16)") (class "Default")
      (node (ref "D4") (pin "16") (pinfunction "PC1_16") (pintype "passive"))
    )
    (net (code "75") (name "unconnected-(D4C-PC2-Pad17)") (class "Default")
      (node (ref "D4") (pin "17") (pinfunction "PC2_17") (pintype "passive"))
    )
    (net (code "76") (name "unconnected-(D4C-PC3-Pad18)") (class "Default")
      (node (ref "D4") (pin "18") (pinfunction "PC3_18") (pintype "passive"))
    )
    (net (code "77") (name "unconnected-(D4C-PC4-Pad33)") (class "Default")
      (node (ref "D4") (pin "33") (pinfunction "PC4_33") (pintype "passive"))
    )
    (net (code "78") (name "unconnected-(D4C-PC5-Pad34)") (class "Default")
      (node (ref "D4") (pin "34") (pinfunction "PC5_34") (pintype "passive"))
    )
    (net (code "79") (name "unconnected-(D4C-PC6-Pad63)") (class "Default")
      (node (ref "D4") (pin "63") (pinfunction "PC6_63") (pintype "passive"))
    )
    (net (code "80") (name "unconnected-(D4C-PC7-Pad64)") (class "Default")
      (node (ref "D4") (pin "64") (pinfunction "PC7_64") (pintype "passive"))
    )
    (net (code "81") (name "unconnected-(D4C-PC8-Pad65)") (class "Default")
      (node (ref "D4") (pin "65") (pinfunction "PC8_65") (pintype "passive"))
    )
    (net (code "82") (name "unconnected-(D4C-PC9-Pad66)") (class "Default")
      (node (ref "D4") (pin "66") (pinfunction "PC9_66") (pintype "passive"))
    )
    (net (code "83") (name "unconnected-(D4C-PC10-Pad78)") (class "Default")
      (node (ref "D4") (pin "78") (pinfunction "PC10_78") (pintype "passive"))
    )
    (net (code "84") (name "unconnected-(D4C-PC11-Pad79)") (class "Default")
      (node (ref "D4") (pin "79") (pinfunction "PC11_79") (pintype "passive"))
    )
    (net (code "85") (name "unconnected-(D4C-PC12-Pad80)") (class "Default")
      (node (ref "D4") (pin "80") (pinfunction "PC12_80") (pintype "passive"))
    )
    (net (code "86") (name "unconnected-(D4C-PC13-Pad7)") (class "Default")
      (node (ref "D4") (pin "7") (pinfunction "PC13_7") (pintype "passive"))
    )
    (net (code "87") (name "unconnected-(D4E-PE0-Pad97)") (class "Default")
      (node (ref "D4") (pin "97") (pinfunction "PE0_97") (pintype "passive"))
    )
    (net (code "88") (name "unconnected-(D4E-PE1-Pad98)") (class "Default")
      (node (ref "D4") (pin "98") (pinfunction "PE1_98") (pintype "passive"))
    )
    (net (code "89") (name "unconnected-(D4E-PE2-Pad1)") (class "Default")
      (node (ref "D4") (pin "1") (pinfunction "PE2_1") (pintype "passive"))
    )
    (net (code "90") (name "unconnected-(D4E-PE5-Pad4)") (class "Default")
      (node (ref "D4") (pin "4") (pinfunction "PE5_4") (pintype "passive"))
    )
    (net (code "91") (name "unconnected-(D4E-PE6-Pad5)") (class "Default")
      (node (ref "D4") (pin "5") (pinfunction "PE6_5") (pintype "passive"))
    )
    (net (code "92") (name "unconnected-(D4E-PE7-Pad38)") (class "Default")
      (node (ref "D4") (pin "38") (pinfunction "PE7_38") (pintype "passive"))
    )
    (net (code "93") (name "unconnected-(D4E-PE8-Pad39)") (class "Default")
      (node (ref "D4") (pin "39") (pinfunction "PE8_39") (pintype "passive"))
    )
    (net (code "94") (name "unconnected-(D4E-PE9-Pad40)") (class "Default")
      (node (ref "D4") (pin "40") (pinfunction "PE9_40") (pintype "passive"))
    )
    (net (code "95") (name "unconnected-(D4E-PE10-Pad41)") (class "Default")
      (node (ref "D4") (pin "41") (pinfunction "PE10_41") (pintype "passive"))
    )
    (net (code "96") (name "unconnected-(D4E-PE11-Pad42)") (class "Default")
      (node (ref "D4") (pin "42") (pinfunction "PE11_42") (pintype "passive"))
    )
    (net (code "97") (name "unconnected-(D4E-PE12-Pad43)") (class "Default")
      (node (ref "D4") (pin "43") (pinfunction "PE12_43") (pintype "passive"))
    )
    (net (code "98") (name "unconnected-(D4E-PE13-Pad44)") (class "Default")
      (node (ref "D4") (pin "44") (pinfunction "PE13_44") (pintype "passive"))
    )
    (net (code "99") (name "unconnected-(D4E-PE14-Pad45)") (class "Default")
      (node (ref "D4") (pin "45") (pinfunction "PE14_45") (pintype "passive"))
    )
    (net (code "100") (name "unconnected-(D4E-PE15-Pad46)") (class "Default")
      (node (ref "D4") (pin "46") (pinfunction "PE15_46") (pintype "passive"))
    )
    (net (code "101") (name "unconnected-(D4F-VBAT-Pad6)") (class "Default")
      (node (ref "D4") (pin "6") (pinfunction "VBAT_6") (pintype "passive"))
    )
  )
)
